# IC555_tao_xung.net
KiCad netlist of a schematic drawn in Altium Designer
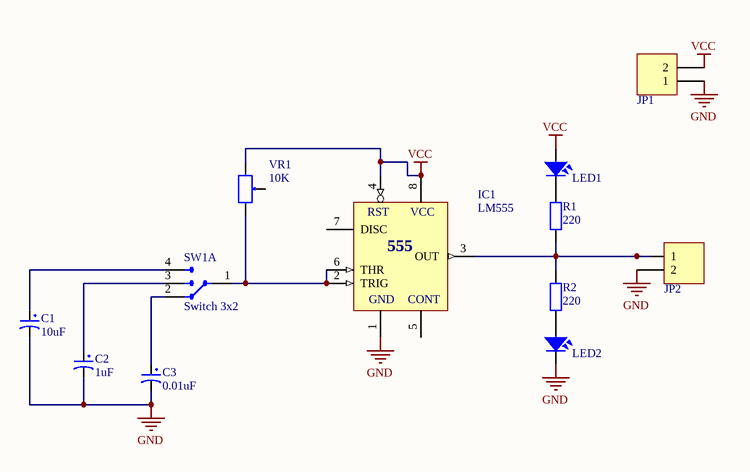
[diagram p0: IC555 tao xung.SchDoc]

(export (version "E")
  (design (tool "Eeschema 10.0.6"))
  (components
    (comp (ref "C1")
      (value "10uF")
      (footprint "CP1.5/3.4")
      (description "Cap 100uF/35V - 470uF/16V")
      (libsource (lib "syhaunguyen") (part "CP3"))
    )
    (comp (ref "C2")
      (value "1uF")
      (footprint "CP1.5/3.4")
      (description "Cap 100uF/35V - 470uF/16V")
      (libsource (lib "syhaunguyen") (part "CP3"))
    )
    (comp (ref "C3")
      (value "0.01uF")
      (footprint "CP1.5/3.4")
      (description "Cap 100uF/35V - 470uF/16V")
      (libsource (lib "syhaunguyen") (part "CP3"))
    )
    (comp (ref "IC1")
      (value "LM555")
      (footprint "DIP8/W0.3")
      (description "Timer")
      (libsource (lib "syhaunguyen") (part "LM555"))
    )
    (comp (ref "JP1")
      (value "Header 2_1")
      (footprint "HED2")
      (description "Header, 2-Pin")
      (fields (field (name "MANUFACTURER") "Generic Components"))
      (libsource (lib "") (part "Header 2_1_1"))
    )
    (comp (ref "JP2")
      (value "Header 2_1")
      (footprint "HED2")
      (description "Header, 2-Pin")
      (fields (field (name "MANUFACTURER") "Generic Components"))
      (libsource (lib "syhaunguyen") (part "Header 2_1"))
    )
    (comp (ref "LED1")
      (value "LED")
      (footprint "LED-3")
      (description "LED Single colour Green and Red")
      (libsource (lib "syhaunguyen") (part "LED"))
    )
    (comp (ref "LED2")
      (value "LED")
      (footprint "LED-3")
      (description "LED Single colour Green and Red")
      (libsource (lib "syhaunguyen") (part "LED"))
    )
    (comp (ref "R1")
      (value "220")
      (footprint "R1/4W")
      (description "Resistor 1/4W")
      (libsource (lib "syhaunguyen") (part "R1/4W"))
    )
    (comp (ref "R2")
      (value "220")
      (footprint "R1/4W")
      (description "Resistor 1/4W")
      (libsource (lib "syhaunguyen") (part "R1/4W"))
    )
    (comp (ref "SW1") (value "Switch 3x2") (footprint "SW3X2") (libsource (lib "syhaunguyen") (part "SW3x2")))
    (comp (ref "VR1")
      (value "10K")
      (footprint "VR")
      (description "Var Resistor")
      (libsource (lib "syhaunguyen") (part "VR"))
    )
  )
  (nets
    (net (code "1") (name "GND") (class "Default")
      (node (ref "C1") (pin "2") (pinfunction "2_2") (pintype "passive"))
      (node (ref "C2") (pin "2") (pinfunction "2_2") (pintype "passive"))
      (node (ref "C3") (pin "2") (pinfunction "2_2") (pintype "passive"))
      (node (ref "IC1") (pin "1") (pinfunction "GND_1") (pintype "power_in"))
      (node (ref "JP1") (pin "1") (pinfunction "1_1") (pintype "passive"))
      (node (ref "JP2") (pin "2") (pinfunction "2_2") (pintype "passive"))
      (node (ref "LED2") (pin "2") (pinfunction "2_2") (pintype "passive"))
    )
    (net (code "2") (name "Net-(IC1-OUT)") (class "Default")
      (node (ref "IC1") (pin "3") (pinfunction "OUT_3") (pintype "output"))
      (node (ref "JP2") (pin "1") (pinfunction "1_1") (pintype "passive"))
      (node (ref "R1") (pin "1") (pinfunction "1_1") (pintype "passive"))
      (node (ref "R2") (pin "2") (pinfunction "2_2") (pintype "passive"))
    )
    (net (code "3") (name "Net-(IC1-THR)") (class "Default")
      (node (ref "IC1") (pin "2") (pinfunction "TRIG_2") (pintype "input"))
      (node (ref "IC1") (pin "6") (pinfunction "THR_6") (pintype "input"))
      (node (ref "SW1") (pin "1") (pinfunction "Com_1") (pintype "passive"))
      (node (ref "VR1") (pin "3") (pinfunction "3_3") (pintype "passive"))
    )
    (net (code "4") (name "Net-(LED1-Pad2)") (class "Default")
      (node (ref "LED1") (pin "2") (pinfunction "2_2") (pintype "passive"))
      (node (ref "R1") (pin "2") (pinfunction "2_2") (pintype "passive"))
    )
    (net (code "5") (name "Net-(LED2-Pad1)") (class "Default")
      (node (ref "LED2") (pin "1") (pinfunction "1_1") (pintype "passive"))
      (node (ref "R2") (pin "1") (pinfunction "1_1") (pintype "passive"))
    )
    (net (code "6") (name "Net-(SW1A-I{slash}O1)") (class "Default")
      (node (ref "C3") (pin "1") (pinfunction "1_1") (pintype "passive"))
      (node (ref "SW1") (pin "2") (pinfunction "I/O1_2") (pintype "passive"))
    )
    (net (code "7") (name "Net-(SW1A-I{slash}O2)") (class "Default")
      (node (ref "C2") (pin "1") (pinfunction "1_1") (pintype "passive"))
      (node (ref "SW1") (pin "3") (pinfunction "I/O2_3") (pintype "passive"))
    )
    (net (code "8") (name "Net-(SW1A-I{slash}O3)") (class "Default")
      (node (ref "C1") (pin "1") (pinfunction "1_1") (pintype "passive"))
      (node (ref "SW1") (pin "4") (pinfunction "I/O3_4") (pintype "passive"))
    )
    (net (code "9") (name "VCC") (class "Default")
      (node (ref "IC1") (pin "4") (pinfunction "RST_4") (pintype "input"))
      (node (ref "IC1") (pin "8") (pinfunction "VCC_8") (pintype "power_in"))
      (node (ref "JP1") (pin "2") (pinfunction "2_2") (pintype "passive"))
      (node (ref "LED1") (pin "1") (pinfunction "1_1") (pintype "passive"))
      (node (ref "VR1") (pin "1") (pinfunction "1_1") (pintype "passive"))
    )
    (net (code "10") (name "unconnected-(IC1-CONT-Pad5)") (class "Default")
      (node (ref "IC1") (pin "5") (pinfunction "CONT_5") (pintype "passive"))
    )
    (net (code "11") (name "unconnected-(IC1-DISC-Pad7)") (class "Default")
      (node (ref "IC1") (pin "7") (pinfunction "DISC_7") (pintype "open_collector"))
    )
    (net (code "12") (name "unconnected-(VR1-Pad2)") (class "Default")
      (node (ref "VR1") (pin "2") (pinfunction "2_2") (pintype "passive"))
    )
  )
)
